# shield100r1.net
KiCad netlist of a schematic drawn in EAGLE
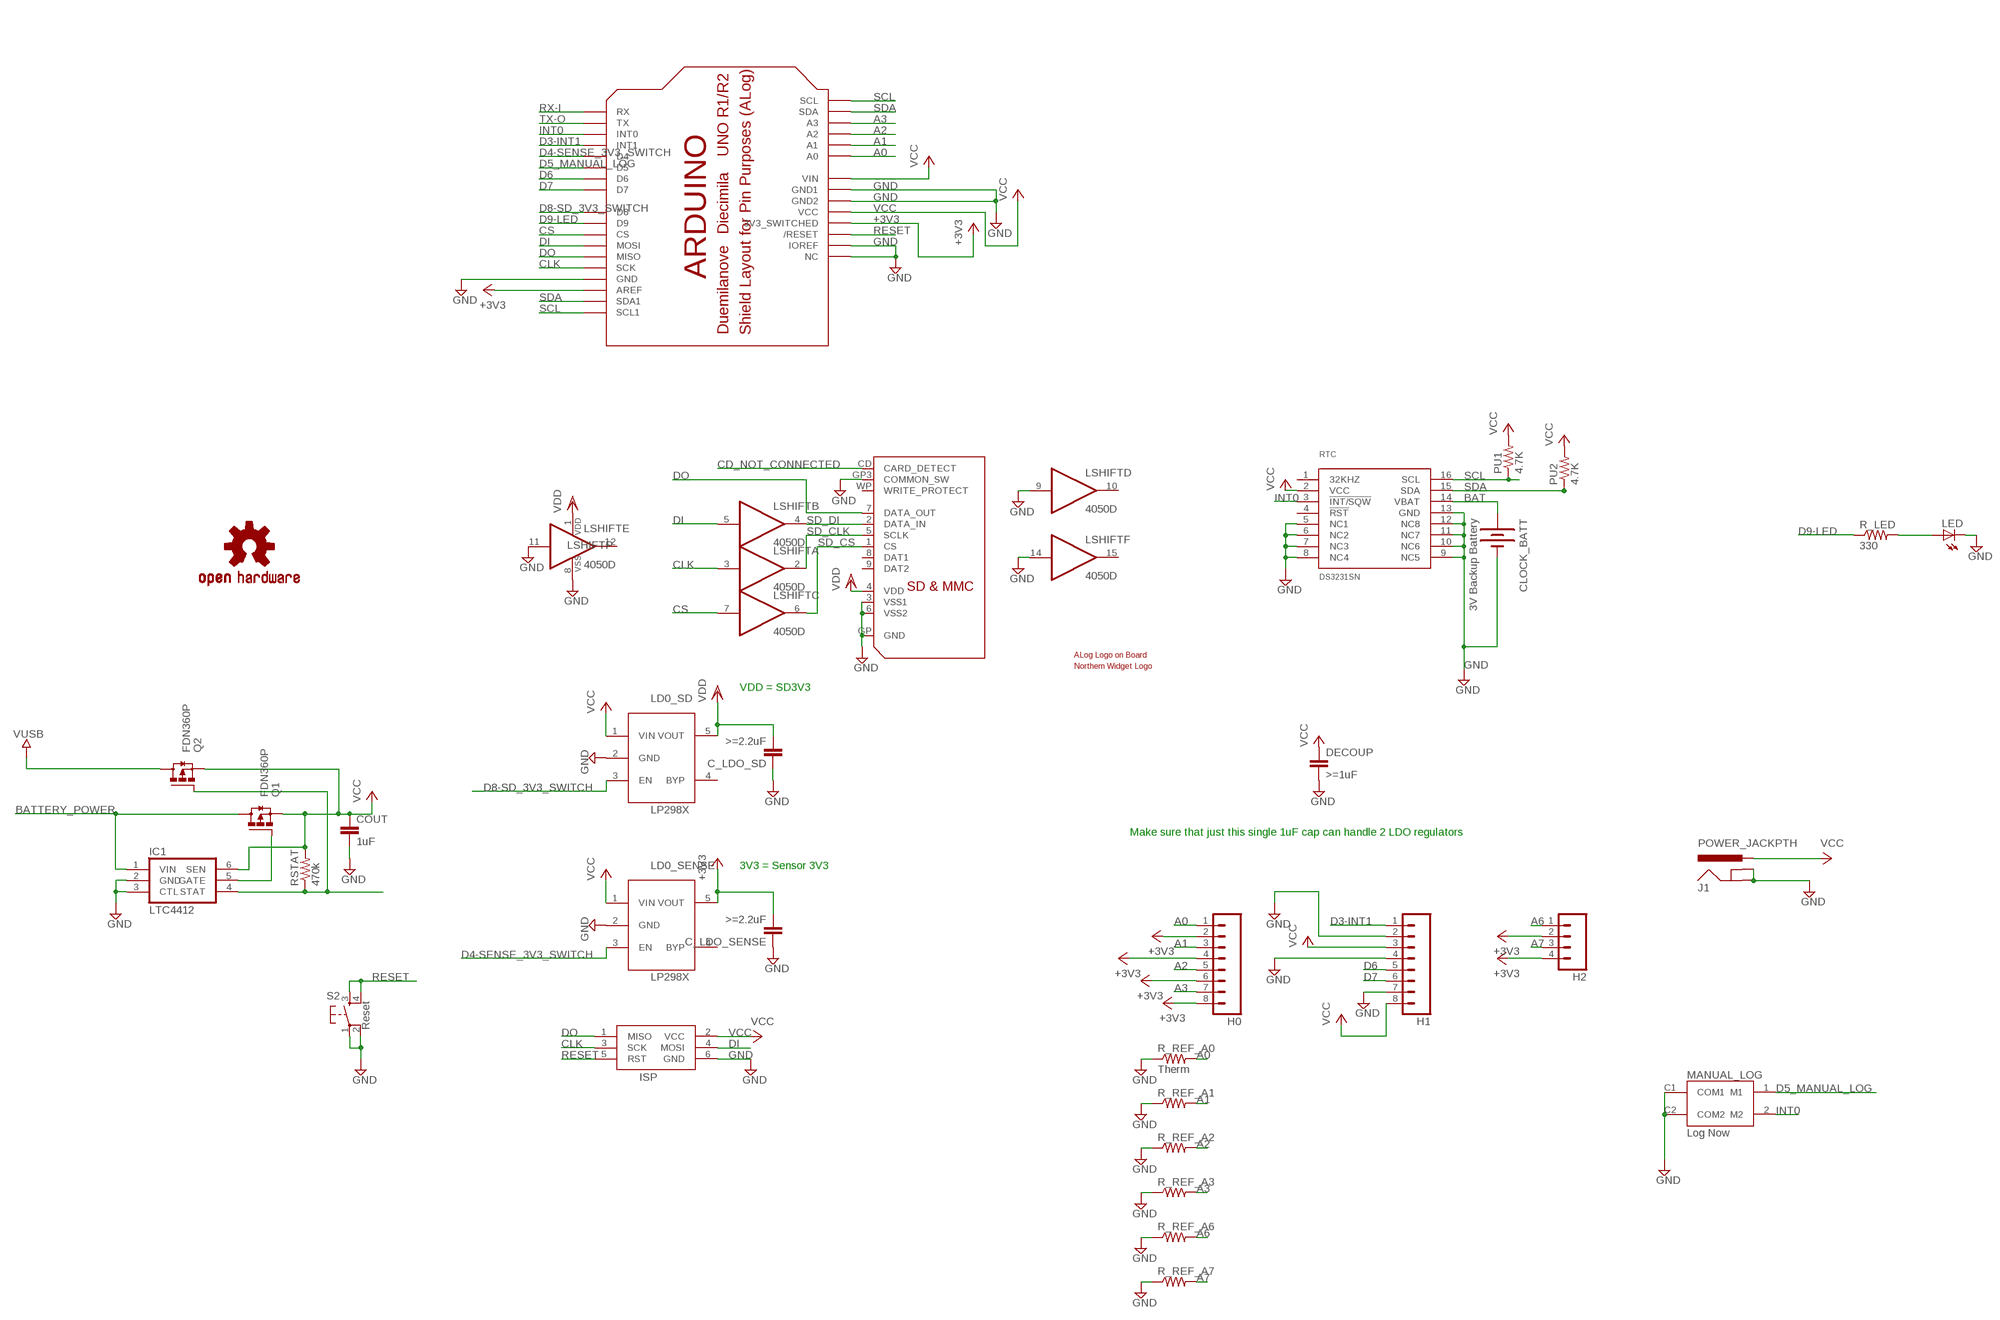
[diagram p0: schematic, sheet 1]

(export (version "E")
  (design (tool "Eeschema 10.0.6"))
  (components
    (comp (ref "CLOCK_BATT")
      (value "3V Backup Battery")
      (footprint "eagle-import:BATTCON_12MM_PTH")
      (libsource (lib "eagle-import") (part "BATTERY12PTH"))
    )
    (comp (ref "COUT")
      (value "1uF")
      (footprint "eagle-import:C0603-ROUND")
      (libsource (lib "eagle-import") (part "C-EUC0603"))
    )
    (comp (ref "C_LDO_SD")
      (value ">=2.2uF")
      (footprint "eagle-import:C0603")
      (libsource (lib "eagle-import") (part "resistor_C-EUC0603"))
    )
    (comp (ref "C_LDO_SENSE")
      (value ">=2.2uF")
      (footprint "eagle-import:C0603")
      (libsource (lib "eagle-import") (part "resistor_C-EUC0603"))
    )
    (comp (ref "DECOUP")
      (value ">=1uF")
      (footprint "eagle-import:C0603")
      (libsource (lib "eagle-import") (part "resistor_C-EUC0603"))
    )
    (comp (ref "H0")
      (value "M083.5MM-8")
      (footprint "eagle-import:SCREWTERMINAL-3.5MM-8")
      (libsource (lib "eagle-import") (part "M083.5MM-8"))
    )
    (comp (ref "H1")
      (value "M083.5MM-8")
      (footprint "eagle-import:SCREWTERMINAL-3.5MM-8")
      (libsource (lib "eagle-import") (part "M083.5MM-8"))
    )
    (comp (ref "H2")
      (value "M04SCREW")
      (footprint "eagle-import:SCREWTERMINAL-3.5MM-4")
      (libsource (lib "eagle-import") (part "M04SCREW"))
    )
    (comp (ref "IC1")
      (value "LTC4412")
      (footprint "eagle-import:TSOT23-6")
      (libsource (lib "eagle-import") (part "LTC4412S6E"))
    )
    (comp (ref "ISP")
      (value "AVRISP-6")
      (footprint "eagle-import:AVRISP")
      (libsource (lib "eagle-import") (part "AVRISP-6"))
    )
    (comp (ref "J1")
      (value "POWER_JACKPTH")
      (footprint "eagle-import:POWER_JACK_PTH")
      (libsource (lib "eagle-import") (part "POWER_JACKPTH"))
    )
    (comp (ref "LD0_SD")
      (value "LP2985")
      (footprint "eagle-import:SOT23-5L")
      (libsource (lib "eagle-import") (part "LP298XS"))
    )
    (comp (ref "LD0_SENSE")
      (value "LP2985")
      (footprint "eagle-import:SOT23-5L")
      (libsource (lib "eagle-import") (part "LP298XS"))
    )
    (comp (ref "LED")
      (value "LED3MM")
      (footprint "eagle-import:LED3MM")
      (libsource (lib "eagle-import") (part "LED3MM"))
    )
    (comp (ref "LOGO1")
      (value "OSHW-LOGOM")
      (footprint "eagle-import:OSHW-LOGO-M")
      (libsource (lib "eagle-import") (part "OSHW-LOGOM"))
    )
    (comp (ref "LSHIFT")
      (value "4050D")
      (footprint "eagle-import:SO16")
      (libsource (lib "eagle-import") (part "4050D"))
    )
    (comp (ref "MANUAL_LOG")
      (value "Log Now")
      (footprint "eagle-import:TL_BUTTON")
      (libsource (lib "eagle-import") (part "TL3350'TL3350'"))
    )
    (comp (ref "PU1")
      (value "4.7K")
      (footprint "eagle-import:R0603")
      (libsource (lib "eagle-import") (part "R-US_R0603"))
    )
    (comp (ref "PU2")
      (value "4.7K")
      (footprint "eagle-import:R0603")
      (libsource (lib "eagle-import") (part "R-US_R0603"))
    )
    (comp (ref "Q1")
      (value "FDN360P")
      (footprint "eagle-import:SUPER-SOT3")
      (libsource (lib "eagle-import") (part "FDN360P"))
    )
    (comp (ref "Q2")
      (value "FDN360P")
      (footprint "eagle-import:SUPER-SOT3")
      (libsource (lib "eagle-import") (part "FDN360P"))
    )
    (comp (ref "RSTAT")
      (value "470k")
      (footprint "eagle-import:R0603")
      (libsource (lib "eagle-import") (part "R-US_R0603"))
    )
    (comp (ref "RTC")
      (value "DS3231SN")
      (footprint "eagle-import:SO16W")
      (libsource (lib "eagle-import") (part "DS3231SN"))
    )
    (comp (ref "R_LED")
      (value "330")
      (footprint "eagle-import:R0603")
      (libsource (lib "eagle-import") (part "R-US_R0603"))
    )
    (comp (ref "R_REF_A0")
      (value "Therm")
      (footprint "eagle-import:0207_10")
      (libsource (lib "eagle-import") (part "resistor_R-US_0207/10"))
    )
    (comp (ref "R_REF_A1")
      (value "R-US_0207/10")
      (footprint "eagle-import:0207_10")
      (libsource (lib "eagle-import") (part "resistor_R-US_0207/10"))
    )
    (comp (ref "R_REF_A2")
      (value "R-US_0207/10")
      (footprint "eagle-import:0207_10")
      (libsource (lib "eagle-import") (part "resistor_R-US_0207/10"))
    )
    (comp (ref "R_REF_A3")
      (value "R-US_0207/10")
      (footprint "eagle-import:0207_10")
      (libsource (lib "eagle-import") (part "resistor_R-US_0207/10"))
    )
    (comp (ref "R_REF_A6")
      (value "R-US_0207/10")
      (footprint "eagle-import:0207_10")
      (libsource (lib "eagle-import") (part "resistor_R-US_0207/10"))
    )
    (comp (ref "R_REF_A7")
      (value "R-US_0207/10")
      (footprint "eagle-import:0207_10")
      (libsource (lib "eagle-import") (part "resistor_R-US_0207/10"))
    )
    (comp (ref "S2")
      (value "Reset")
      (footprint "eagle-import:TACTILE_SWITCH_SMD")
      (libsource (lib "eagle-import") (part "TAC_SWITCHSND"))
    )
    (comp (ref "SD")
      (value "SDMMC06132")
      (footprint "eagle-import:06132")
      (libsource (lib "eagle-import") (part "SDMMC06132"))
    )
    (comp (ref "U$2")
      (value "ALOG_LOGO_V1_5.5MM")
      (footprint "eagle-import:ALOG_LOGO_V1_SMALL")
      (libsource (lib "eagle-import") (part "ALOG_LOGO_V1_5.5MM"))
    )
    (comp (ref "U$3")
      (value "NWLOGO_MED")
      (footprint "eagle-import:NWLOGO_MED")
      (libsource (lib "eagle-import") (part "NWLOGO_MED"))
    )
    (comp (ref "U$9")
      (value "ARDUINO_SHIELD_PIN_PURPOSE")
      (footprint "eagle-import:ARDUINO_SHIELD_PINS_ONLY")
      (libsource (lib "eagle-import") (part "ARDUINO_SHIELD_PIN_PURPOSE"))
    )
  )
  (nets
    (net (code "1") (name "+3V3") (class "Default")
      (node (ref "C_LDO_SENSE") (pin "2") (pinfunction "2_2") (pintype "passive"))
      (node (ref "H0") (pin "2") (pinfunction "2_2") (pintype "passive"))
      (node (ref "H0") (pin "4") (pinfunction "4_4") (pintype "passive"))
      (node (ref "H0") (pin "6") (pinfunction "6_6") (pintype "passive"))
      (node (ref "H0") (pin "8") (pinfunction "8_8") (pintype "passive"))
      (node (ref "H2") (pin "2") (pinfunction "2_2") (pintype "passive"))
      (node (ref "H2") (pin "4") (pinfunction "4_4") (pintype "passive"))
      (node (ref "LD0_SENSE") (pin "5") (pinfunction "VOUT_5") (pintype "bidirectional"))
      (node (ref "U$9") (pin "3.3V") (pinfunction "3V3_SWITCHED_3.3V") (pintype "power_in"))
      (node (ref "U$9") (pin "AREF") (pinfunction "AREF_AREF") (pintype "bidirectional"))
    )
    (net (code "2") (name "/A0") (class "Default")
      (node (ref "H0") (pin "1") (pinfunction "1_1") (pintype "passive"))
      (node (ref "R_REF_A0") (pin "2") (pinfunction "2_2") (pintype "passive"))
      (node (ref "U$9") (pin "A0") (pinfunction "A0_A0") (pintype "bidirectional"))
    )
    (net (code "3") (name "/A1") (class "Default")
      (node (ref "H0") (pin "3") (pinfunction "3_3") (pintype "passive"))
      (node (ref "R_REF_A1") (pin "2") (pinfunction "2_2") (pintype "passive"))
      (node (ref "U$9") (pin "A1") (pinfunction "A1_A1") (pintype "bidirectional"))
    )
    (net (code "4") (name "/A2") (class "Default")
      (node (ref "H0") (pin "5") (pinfunction "5_5") (pintype "passive"))
      (node (ref "R_REF_A2") (pin "2") (pinfunction "2_2") (pintype "passive"))
      (node (ref "U$9") (pin "A2") (pinfunction "A2_A2") (pintype "bidirectional"))
    )
    (net (code "5") (name "/A3") (class "Default")
      (node (ref "H0") (pin "7") (pinfunction "7_7") (pintype "passive"))
      (node (ref "R_REF_A3") (pin "2") (pinfunction "2_2") (pintype "passive"))
      (node (ref "U$9") (pin "A3") (pinfunction "A3_A3") (pintype "bidirectional"))
    )
    (net (code "6") (name "/A6") (class "Default")
      (node (ref "H2") (pin "1") (pinfunction "1_1") (pintype "passive"))
      (node (ref "R_REF_A6") (pin "2") (pinfunction "2_2") (pintype "passive"))
    )
    (net (code "7") (name "/A7") (class "Default")
      (node (ref "H2") (pin "3") (pinfunction "3_3") (pintype "passive"))
      (node (ref "R_REF_A7") (pin "2") (pinfunction "2_2") (pintype "passive"))
    )
    (net (code "8") (name "/BAT") (class "Default")
      (node (ref "CLOCK_BATT") (pin "VCC@1") (pinfunction "+_VCC@1") (pintype "power_in"))
      (node (ref "RTC") (pin "14") (pinfunction "VBAT_14") (pintype "bidirectional"))
    )
    (net (code "9") (name "/BATTERY_POWER") (class "Default")
      (node (ref "IC1") (pin "1") (pinfunction "VIN_1") (pintype "input"))
      (node (ref "Q1") (pin "3") (pinfunction "D_3") (pintype "passive"))
    )
    (net (code "10") (name "/CD_NOT_CONNECTED") (class "Default")
      (node (ref "SD") (pin "CD") (pinfunction "CARD_DETECT_CD") (pintype "passive"))
    )
    (net (code "11") (name "/CLK") (class "Default")
      (node (ref "ISP") (pin "3") (pinfunction "SCK_3") (pintype "output"))
      (node (ref "LSHIFT") (pin "3") (pinfunction "I_3") (pintype "input"))
      (node (ref "U$9") (pin "D13") (pinfunction "SCK_D13") (pintype "bidirectional"))
    )
    (net (code "12") (name "/CS") (class "Default")
      (node (ref "LSHIFT") (pin "7") (pinfunction "I_7") (pintype "input"))
      (node (ref "U$9") (pin "D10") (pinfunction "CS_D10") (pintype "bidirectional"))
    )
    (net (code "13") (name "/D3-INT1") (class "Default")
      (node (ref "H1") (pin "1") (pinfunction "1_1") (pintype "passive"))
      (node (ref "U$9") (pin "D3") (pinfunction "INT1_D3") (pintype "bidirectional"))
    )
    (net (code "14") (name "/D4-SENSE_3V3_SWITCH") (class "Default")
      (node (ref "LD0_SENSE") (pin "3") (pinfunction "EN_3") (pintype "bidirectional"))
      (node (ref "U$9") (pin "D4") (pinfunction "D4_D4") (pintype "bidirectional"))
    )
    (net (code "15") (name "/D5_MANUAL_LOG") (class "Default")
      (node (ref "MANUAL_LOG") (pin "1") (pinfunction "M1_1") (pintype "bidirectional"))
      (node (ref "U$9") (pin "D5") (pinfunction "D5_D5") (pintype "bidirectional"))
    )
    (net (code "16") (name "/D6") (class "Default")
      (node (ref "H1") (pin "5") (pinfunction "5_5") (pintype "passive"))
      (node (ref "U$9") (pin "D6") (pinfunction "D6_D6") (pintype "bidirectional"))
    )
    (net (code "17") (name "/D7") (class "Default")
      (node (ref "H1") (pin "6") (pinfunction "6_6") (pintype "passive"))
      (node (ref "U$9") (pin "D7") (pinfunction "D7_D7") (pintype "bidirectional"))
    )
    (net (code "18") (name "/D8-SD_3V3_SWITCH") (class "Default")
      (node (ref "LD0_SD") (pin "3") (pinfunction "EN_3") (pintype "bidirectional"))
      (node (ref "U$9") (pin "D8") (pinfunction "D8_D8") (pintype "bidirectional"))
    )
    (net (code "19") (name "/D9-LED") (class "Default")
      (node (ref "R_LED") (pin "1") (pinfunction "1_1") (pintype "passive"))
      (node (ref "U$9") (pin "D9") (pinfunction "D9_D9") (pintype "bidirectional"))
    )
    (net (code "20") (name "/DI") (class "Default")
      (node (ref "ISP") (pin "4") (pinfunction "MOSI_4") (pintype "output"))
      (node (ref "LSHIFT") (pin "5") (pinfunction "I_5") (pintype "input"))
      (node (ref "U$9") (pin "D11") (pinfunction "MOSI_D11") (pintype "bidirectional"))
    )
    (net (code "21") (name "/DO") (class "Default")
      (node (ref "ISP") (pin "1") (pinfunction "MISO_1") (pintype "input"))
      (node (ref "SD") (pin "7") (pinfunction "DATA_OUT_7") (pintype "output"))
      (node (ref "U$9") (pin "D12") (pinfunction "MISO_D12") (pintype "bidirectional"))
    )
    (net (code "22") (name "/INT0") (class "Default")
      (node (ref "MANUAL_LOG") (pin "2") (pinfunction "M2_2") (pintype "bidirectional"))
      (node (ref "RTC") (pin "3") (pinfunction "~{INT/SQW}_3") (pintype "bidirectional"))
      (node (ref "U$9") (pin "D2") (pinfunction "INT0_D2") (pintype "bidirectional"))
    )
    (net (code "23") (name "/RESET") (class "Default")
      (node (ref "ISP") (pin "5") (pinfunction "RST_5") (pintype "output"))
      (node (ref "S2") (pin "3") (pinfunction "3_3") (pintype "passive"))
      (node (ref "S2") (pin "4") (pinfunction "4_4") (pintype "passive"))
      (node (ref "U$9") (pin "RES") (pinfunction "/RESET_RES") (pintype "bidirectional"))
    )
    (net (code "24") (name "/RX-I") (class "Default")
      (node (ref "U$9") (pin "RX") (pinfunction "RX_RX") (pintype "bidirectional"))
    )
    (net (code "25") (name "/SCL") (class "Default")
      (node (ref "PU1") (pin "1") (pinfunction "1_1") (pintype "passive"))
      (node (ref "RTC") (pin "16") (pinfunction "SCL_16") (pintype "bidirectional"))
      (node (ref "U$9") (pin "A5") (pinfunction "SCL_A5") (pintype "bidirectional"))
      (node (ref "U$9") (pin "SCL") (pinfunction "SCL1_SCL") (pintype "bidirectional"))
    )
    (net (code "26") (name "/SDA") (class "Default")
      (node (ref "PU2") (pin "1") (pinfunction "1_1") (pintype "passive"))
      (node (ref "RTC") (pin "15") (pinfunction "SDA_15") (pintype "bidirectional"))
      (node (ref "U$9") (pin "A4") (pinfunction "SDA_A4") (pintype "bidirectional"))
      (node (ref "U$9") (pin "SDA") (pinfunction "SDA1_SDA") (pintype "bidirectional"))
    )
    (net (code "27") (name "/SD_CLK") (class "Default")
      (node (ref "LSHIFT") (pin "2") (pinfunction "O_2") (pintype "output"))
      (node (ref "SD") (pin "5") (pinfunction "SCLK_5") (pintype "input"))
    )
    (net (code "28") (name "/SD_CS") (class "Default")
      (node (ref "LSHIFT") (pin "6") (pinfunction "O_6") (pintype "output"))
      (node (ref "SD") (pin "1") (pinfunction "CS_1") (pintype "input"))
    )
    (net (code "29") (name "/SD_DI") (class "Default")
      (node (ref "LSHIFT") (pin "4") (pinfunction "O_4") (pintype "output"))
      (node (ref "SD") (pin "2") (pinfunction "DATA_IN_2") (pintype "input"))
    )
    (net (code "30") (name "/TX-O") (class "Default")
      (node (ref "U$9") (pin "TX") (pinfunction "TX_TX") (pintype "bidirectional"))
    )
    (net (code "31") (name "GND") (class "Default")
      (node (ref "CLOCK_BATT") (pin "GND") (pinfunction "-_GND") (pintype "power_in"))
      (node (ref "COUT") (pin "2") (pinfunction "2_2") (pintype "passive"))
      (node (ref "C_LDO_SD") (pin "1") (pinfunction "1_1") (pintype "passive"))
      (node (ref "C_LDO_SENSE") (pin "1") (pinfunction "1_1") (pintype "passive"))
      (node (ref "DECOUP") (pin "2") (pinfunction "2_2") (pintype "passive"))
      (node (ref "H1") (pin "2") (pinfunction "2_2") (pintype "passive"))
      (node (ref "H1") (pin "4") (pinfunction "4_4") (pintype "passive"))
      (node (ref "H1") (pin "7") (pinfunction "7_7") (pintype "passive"))
      (node (ref "IC1") (pin "2") (pinfunction "GND_2") (pintype "passive"))
      (node (ref "IC1") (pin "3") (pinfunction "CTL_3") (pintype "input"))
      (node (ref "ISP") (pin "6") (pinfunction "GND_6") (pintype "power_in"))
      (node (ref "J1") (pin "GND") (pinfunction "GND_GND") (pintype "bidirectional"))
      (node (ref "J1") (pin "GNDBREAK") (pinfunction "GNDBREAK_GNDBREAK") (pintype "bidirectional"))
      (node (ref "LD0_SD") (pin "2") (pinfunction "GND_2") (pintype "bidirectional"))
      (node (ref "LD0_SENSE") (pin "2") (pinfunction "GND_2") (pintype "bidirectional"))
      (node (ref "LED") (pin "K") (pinfunction "C_K") (pintype "passive"))
      (node (ref "LSHIFT") (pin "11") (pinfunction "I_11") (pintype "input"))
      (node (ref "LSHIFT") (pin "14") (pinfunction "I_14") (pintype "input"))
      (node (ref "LSHIFT") (pin "8") (pinfunction "VSS_8") (pintype "power_in"))
      (node (ref "LSHIFT") (pin "9") (pinfunction "I_9") (pintype "input"))
      (node (ref "MANUAL_LOG") (pin "C1") (pinfunction "COM1_C1") (pintype "bidirectional"))
      (node (ref "MANUAL_LOG") (pin "C2") (pinfunction "COM2_C2") (pintype "bidirectional"))
      (node (ref "RTC") (pin "10") (pinfunction "NC6_10") (pintype "bidirectional"))
      (node (ref "RTC") (pin "11") (pinfunction "NC7_11") (pintype "bidirectional"))
      (node (ref "RTC") (pin "12") (pinfunction "NC8_12") (pintype "bidirectional"))
      (node (ref "RTC") (pin "13") (pinfunction "GND_13") (pintype "bidirectional"))
      (node (ref "RTC") (pin "5") (pinfunction "NC1_5") (pintype "bidirectional"))
      (node (ref "RTC") (pin "6") (pinfunction "NC2_6") (pintype "bidirectional"))
      (node (ref "RTC") (pin "7") (pinfunction "NC3_7") (pintype "bidirectional"))
      (node (ref "RTC") (pin "8") (pinfunction "NC4_8") (pintype "bidirectional"))
      (node (ref "RTC") (pin "9") (pinfunction "NC5_9") (pintype "bidirectional"))
      (node (ref "R_REF_A0") (pin "1") (pinfunction "1_1") (pintype "passive"))
      (node (ref "R_REF_A1") (pin "1") (pinfunction "1_1") (pintype "passive"))
      (node (ref "R_REF_A2") (pin "1") (pinfunction "1_1") (pintype "passive"))
      (node (ref "R_REF_A3") (pin "1") (pinfunction "1_1") (pintype "passive"))
      (node (ref "R_REF_A6") (pin "1") (pinfunction "1_1") (pintype "passive"))
      (node (ref "R_REF_A7") (pin "1") (pinfunction "1_1") (pintype "passive"))
      (node (ref "S2") (pin "1") (pinfunction "1_1") (pintype "passive"))
      (node (ref "S2") (pin "2") (pinfunction "2_2") (pintype "passive"))
      (node (ref "SD") (pin "3") (pinfunction "VSS1_3") (pintype "power_in"))
      (node (ref "SD") (pin "6") (pinfunction "VSS2_6") (pintype "power_in"))
      (node (ref "SD") (pin "GP") (pinfunction "GND_GP") (pintype "power_in"))
      (node (ref "SD") (pin "GP3") (pinfunction "COMMON_SW_GP3") (pintype "passive"))
      (node (ref "U$9") (pin "GND@0") (pinfunction "GND_GND@0") (pintype "power_in"))
      (node (ref "U$9") (pin "GND@1") (pinfunction "GND1_GND@1") (pintype "power_in"))
      (node (ref "U$9") (pin "GND@2") (pinfunction "GND2_GND@2") (pintype "power_in"))
      (node (ref "U$9") (pin "IOREF") (pinfunction "IOREF_IOREF") (pintype "bidirectional"))
      (node (ref "U$9") (pin "NC") (pinfunction "NC_NC") (pintype "bidirectional"))
    )
    (net (code "32") (name "Net-(IC1-GATE)") (class "Default")
      (node (ref "IC1") (pin "5") (pinfunction "GATE_5") (pintype "output"))
      (node (ref "Q1") (pin "1") (pinfunction "G_1") (pintype "passive"))
    )
    (net (code "33") (name "Net-(IC1-STAT)") (class "Default")
      (node (ref "IC1") (pin "4") (pinfunction "STAT_4") (pintype "open_collector"))
      (node (ref "Q2") (pin "1") (pinfunction "G_1") (pintype "passive"))
      (node (ref "RSTAT") (pin "1") (pinfunction "1_1") (pintype "passive"))
    )
    (net (code "34") (name "Net-(LED-PadA)") (class "Default")
      (node (ref "LED") (pin "A") (pinfunction "A_A") (pintype "passive"))
      (node (ref "R_LED") (pin "2") (pinfunction "2_2") (pintype "passive"))
    )
    (net (code "35") (name "VCC") (class "Default")
      (node (ref "COUT") (pin "1") (pinfunction "1_1") (pintype "passive"))
      (node (ref "DECOUP") (pin "1") (pinfunction "1_1") (pintype "passive"))
      (node (ref "H1") (pin "3") (pinfunction "3_3") (pintype "passive"))
      (node (ref "H1") (pin "8") (pinfunction "8_8") (pintype "passive"))
      (node (ref "IC1") (pin "6") (pinfunction "SEN_6") (pintype "input"))
      (node (ref "ISP") (pin "2") (pinfunction "VCC_2") (pintype "power_in"))
      (node (ref "J1") (pin "PWR") (pinfunction "PWR_PWR") (pintype "bidirectional"))
      (node (ref "LD0_SD") (pin "1") (pinfunction "VIN_1") (pintype "bidirectional"))
      (node (ref "LD0_SENSE") (pin "1") (pinfunction "VIN_1") (pintype "bidirectional"))
      (node (ref "PU1") (pin "2") (pinfunction "2_2") (pintype "passive"))
      (node (ref "PU2") (pin "2") (pinfunction "2_2") (pintype "passive"))
      (node (ref "Q1") (pin "2") (pinfunction "S_2") (pintype "passive"))
      (node (ref "Q2") (pin "2") (pinfunction "S_2") (pintype "passive"))
      (node (ref "RSTAT") (pin "2") (pinfunction "2_2") (pintype "passive"))
      (node (ref "RTC") (pin "2") (pinfunction "VCC_2") (pintype "bidirectional"))
      (node (ref "U$9") (pin "5V") (pinfunction "VCC_5V") (pintype "power_in"))
      (node (ref "U$9") (pin "VIN") (pinfunction "VIN_VIN") (pintype "power_in"))
    )
    (net (code "36") (name "VDD") (class "Default")
      (node (ref "C_LDO_SD") (pin "2") (pinfunction "2_2") (pintype "passive"))
      (node (ref "LD0_SD") (pin "5") (pinfunction "VOUT_5") (pintype "bidirectional"))
      (node (ref "LSHIFT") (pin "1") (pinfunction "VDD_1") (pintype "power_in"))
      (node (ref "SD") (pin "4") (pinfunction "VDD_4") (pintype "power_in"))
    )
    (net (code "37") (name "VUSB") (class "Default")
      (node (ref "Q2") (pin "3") (pinfunction "D_3") (pintype "passive"))
    )
    (net (code "38") (name "unconnected-(LD0_SD-BYP-Pad4)") (class "Default")
      (node (ref "LD0_SD") (pin "4") (pinfunction "BYP_4") (pintype "bidirectional"))
    )
    (net (code "39") (name "unconnected-(LD0_SENSE-BYP-Pad4)") (class "Default")
      (node (ref "LD0_SENSE") (pin "4") (pinfunction "BYP_4") (pintype "bidirectional"))
    )
    (net (code "40") (name "unconnected-(LSHIFTD-O-Pad10)") (class "Default")
      (node (ref "LSHIFT") (pin "10") (pinfunction "O_10") (pintype "output"))
    )
    (net (code "41") (name "unconnected-(LSHIFTE-O-Pad12)") (class "Default")
      (node (ref "LSHIFT") (pin "12") (pinfunction "O_12") (pintype "output"))
    )
    (net (code "42") (name "unconnected-(LSHIFTF-O-Pad15)") (class "Default")
      (node (ref "LSHIFT") (pin "15") (pinfunction "O_15") (pintype "output"))
    )
    (net (code "43") (name "unconnected-(RTC-32KHZ-Pad1)") (class "Default")
      (node (ref "RTC") (pin "1") (pinfunction "32KHZ_1") (pintype "bidirectional"))
    )
    (net (code "44") (name "unconnected-(RTC-~{RST}-Pad4)") (class "Default")
      (node (ref "RTC") (pin "4") (pinfunction "~{RST}_4") (pintype "bidirectional"))
    )
    (net (code "45") (name "unconnected-(SD-DAT1-Pad8)") (class "Default")
      (node (ref "SD") (pin "8") (pinfunction "DAT1_8") (pintype "bidirectional"))
    )
    (net (code "46") (name "unconnected-(SD-DAT2-Pad9)") (class "Default")
      (node (ref "SD") (pin "9") (pinfunction "DAT2_9") (pintype "bidirectional"))
    )
    (net (code "47") (name "unconnected-(SD-WRITE_PROTECT-PadWP)") (class "Default")
      (node (ref "SD") (pin "WP") (pinfunction "WRITE_PROTECT_WP") (pintype "passive"))
    )
  )
)
